# Sheet1.net
KiCad netlist of a schematic drawn in Altium Designer
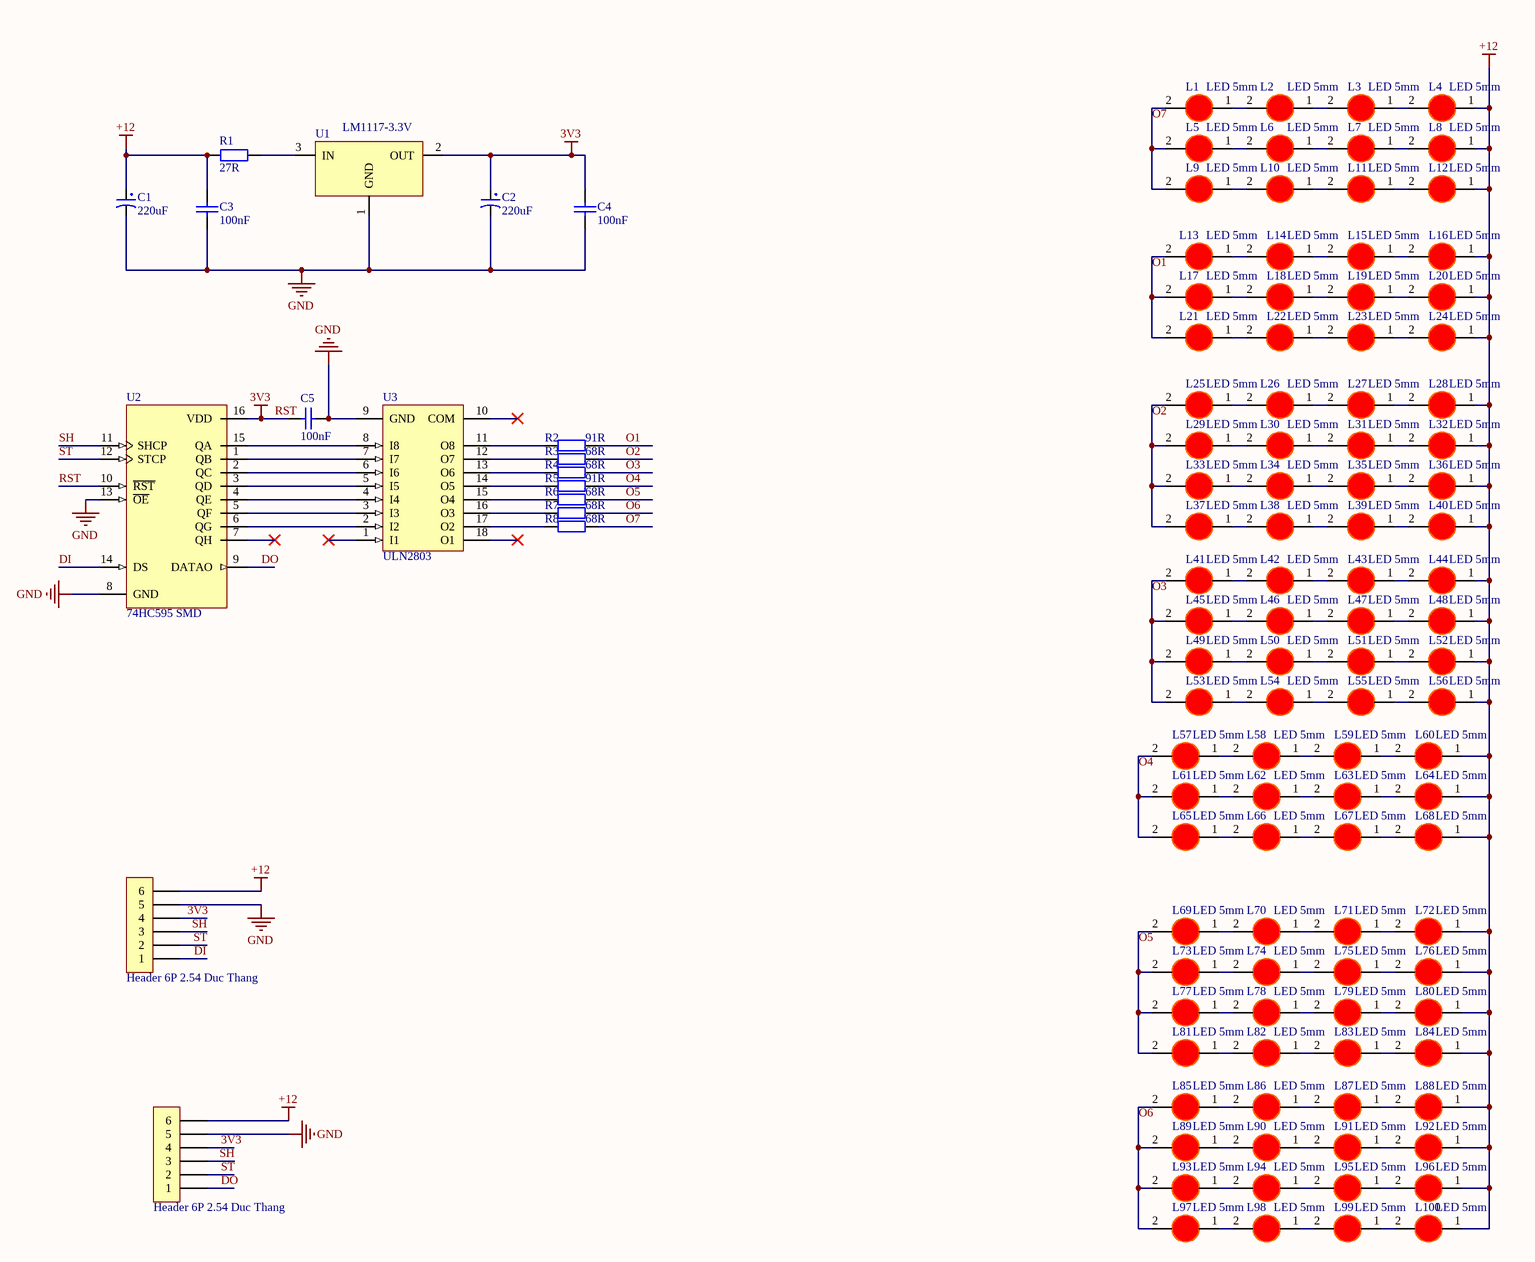
[diagram p0: Sheet1.SchDoc]

(export (version "E")
  (design (tool "Eeschema 10.0.6"))
  (components
    (comp (ref "C1")
      (value "220uF")
      (footprint "Tu hoa 5mm")
      (description "Cắm")
      (libsource (lib "Altium_Lib_by_KhueNguyenCreator") (part "Tu Hoa 220uF 16V 6x11"))
    )
    (comp (ref "C2")
      (value "220uF")
      (footprint "Tu hoa 5mm")
      (description "Cắm")
      (libsource (lib "Altium_Lib_by_KhueNguyenCreator") (part "Tu Hoa 220uF 16V 6x11"))
    )
    (comp (ref "C3")
      (value "100nF")
      (footprint "tu 0805")
      (description "Dán")
      (libsource (lib "Altium_Lib_by_KhueNguyenCreator") (part "Tu 0805 101 50V 20%"))
    )
    (comp (ref "C4")
      (value "100nF")
      (footprint "tu 0805")
      (description "Dán")
      (libsource (lib "Altium_Lib_by_KhueNguyenCreator") (part "Tu 0805 101 50V 20%"))
    )
    (comp (ref "C5")
      (value "100nF")
      (footprint "tu 0805")
      (description "Dán")
      (libsource (lib "Altium_Lib_by_KhueNguyenCreator") (part "Tu 0805 101 50V 20%"))
    )
    (comp (ref "H1")
      (value "Header 6P 2.54 Duc Thang")
      (footprint "XH2.54M-6")
      (description "Cắm")
      (libsource (lib "Altium_Lib_by_KhueNguyenCreator") (part "Header 6P 2.54 Duc Thang"))
    )
    (comp (ref "H2")
      (value "Header 6P 2.54 Duc Thang")
      (footprint "XH2.54M-6")
      (description "Cắm")
      (libsource (lib "Altium_Lib_by_KhueNguyenCreator") (part "Header 6P 2.54 Duc Thang"))
    )
    (comp (ref "L1")
      (value "LED 5mm")
      (footprint "LED-5MM-RED")
      (description "Cắm")
      (libsource (lib "Altium_Lib_by_KhueNguyenCreator") (part "LED 5mm Do"))
    )
    (comp (ref "L2")
      (value "LED 5mm")
      (footprint "LED-5MM-RED")
      (description "Cắm")
      (libsource (lib "Altium_Lib_by_KhueNguyenCreator") (part "LED 5mm Do"))
    )
    (comp (ref "L3")
      (value "LED 5mm")
      (footprint "LED-5MM-RED")
      (description "Cắm")
      (libsource (lib "Altium_Lib_by_KhueNguyenCreator") (part "LED 5mm Do"))
    )
    (comp (ref "L4")
      (value "LED 5mm")
      (footprint "LED-5MM-RED")
      (description "Cắm")
      (libsource (lib "Altium_Lib_by_KhueNguyenCreator") (part "LED 5mm Do"))
    )
    (comp (ref "L5")
      (value "LED 5mm")
      (footprint "LED-5MM-RED")
      (description "Cắm")
      (libsource (lib "Altium_Lib_by_KhueNguyenCreator") (part "LED 5mm Do"))
    )
    (comp (ref "L6")
      (value "LED 5mm")
      (footprint "LED-5MM-RED")
      (description "Cắm")
      (libsource (lib "Altium_Lib_by_KhueNguyenCreator") (part "LED 5mm Do"))
    )
    (comp (ref "L7")
      (value "LED 5mm")
      (footprint "LED-5MM-RED")
      (description "Cắm")
      (libsource (lib "Altium_Lib_by_KhueNguyenCreator") (part "LED 5mm Do"))
    )
    (comp (ref "L8")
      (value "LED 5mm")
      (footprint "LED-5MM-RED")
      (description "Cắm")
      (libsource (lib "Altium_Lib_by_KhueNguyenCreator") (part "LED 5mm Do"))
    )
    (comp (ref "L9")
      (value "LED 5mm")
      (footprint "LED-5MM-RED")
      (description "Cắm")
      (libsource (lib "Altium_Lib_by_KhueNguyenCreator") (part "LED 5mm Do"))
    )
    (comp (ref "L10")
      (value "LED 5mm")
      (footprint "LED-5MM-RED")
      (description "Cắm")
      (libsource (lib "Altium_Lib_by_KhueNguyenCreator") (part "LED 5mm Do"))
    )
    (comp (ref "L11")
      (value "LED 5mm")
      (footprint "LED-5MM-RED")
      (description "Cắm")
      (libsource (lib "Altium_Lib_by_KhueNguyenCreator") (part "LED 5mm Do"))
    )
    (comp (ref "L12")
      (value "LED 5mm")
      (footprint "LED-5MM-RED")
      (description "Cắm")
      (libsource (lib "Altium_Lib_by_KhueNguyenCreator") (part "LED 5mm Do"))
    )
    (comp (ref "L13")
      (value "LED 5mm")
      (footprint "LED-5MM-RED")
      (description "Cắm")
      (libsource (lib "Altium_Lib_by_KhueNguyenCreator") (part "LED 5mm Do"))
    )
    (comp (ref "L14")
      (value "LED 5mm")
      (footprint "LED-5MM-RED")
      (description "Cắm")
      (libsource (lib "Altium_Lib_by_KhueNguyenCreator") (part "LED 5mm Do"))
    )
    (comp (ref "L15")
      (value "LED 5mm")
      (footprint "LED-5MM-RED")
      (description "Cắm")
      (libsource (lib "Altium_Lib_by_KhueNguyenCreator") (part "LED 5mm Do"))
    )
    (comp (ref "L16")
      (value "LED 5mm")
      (footprint "LED-5MM-RED")
      (description "Cắm")
      (libsource (lib "Altium_Lib_by_KhueNguyenCreator") (part "LED 5mm Do"))
    )
    (comp (ref "L17")
      (value "LED 5mm")
      (footprint "LED-5MM-RED")
      (description "Cắm")
      (libsource (lib "Altium_Lib_by_KhueNguyenCreator") (part "LED 5mm Do"))
    )
    (comp (ref "L18")
      (value "LED 5mm")
      (footprint "LED-5MM-RED")
      (description "Cắm")
      (libsource (lib "Altium_Lib_by_KhueNguyenCreator") (part "LED 5mm Do"))
    )
    (comp (ref "L19")
      (value "LED 5mm")
      (footprint "LED-5MM-RED")
      (description "Cắm")
      (libsource (lib "Altium_Lib_by_KhueNguyenCreator") (part "LED 5mm Do"))
    )
    (comp (ref "L20")
      (value "LED 5mm")
      (footprint "LED-5MM-RED")
      (description "Cắm")
      (libsource (lib "Altium_Lib_by_KhueNguyenCreator") (part "LED 5mm Do"))
    )
    (comp (ref "L21")
      (value "LED 5mm")
      (footprint "LED-5MM-RED")
      (description "Cắm")
      (libsource (lib "Altium_Lib_by_KhueNguyenCreator") (part "LED 5mm Do"))
    )
    (comp (ref "L22")
      (value "LED 5mm")
      (footprint "LED-5MM-RED")
      (description "Cắm")
      (libsource (lib "Altium_Lib_by_KhueNguyenCreator") (part "LED 5mm Do"))
    )
    (comp (ref "L23")
      (value "LED 5mm")
      (footprint "LED-5MM-RED")
      (description "Cắm")
      (libsource (lib "Altium_Lib_by_KhueNguyenCreator") (part "LED 5mm Do"))
    )
    (comp (ref "L24")
      (value "LED 5mm")
      (footprint "LED-5MM-RED")
      (description "Cắm")
      (libsource (lib "Altium_Lib_by_KhueNguyenCreator") (part "LED 5mm Do"))
    )
    (comp (ref "L25")
      (value "LED 5mm")
      (footprint "LED-5MM-RED")
      (description "Cắm")
      (libsource (lib "Altium_Lib_by_KhueNguyenCreator") (part "LED 5mm Do"))
    )
    (comp (ref "L26")
      (value "LED 5mm")
      (footprint "LED-5MM-RED")
      (description "Cắm")
      (libsource (lib "Altium_Lib_by_KhueNguyenCreator") (part "LED 5mm Do"))
    )
    (comp (ref "L27")
      (value "LED 5mm")
      (footprint "LED-5MM-RED")
      (description "Cắm")
      (libsource (lib "Altium_Lib_by_KhueNguyenCreator") (part "LED 5mm Do"))
    )
    (comp (ref "L28")
      (value "LED 5mm")
      (footprint "LED-5MM-RED")
      (description "Cắm")
      (libsource (lib "Altium_Lib_by_KhueNguyenCreator") (part "LED 5mm Do"))
    )
    (comp (ref "L29")
      (value "LED 5mm")
      (footprint "LED-5MM-RED")
      (description "Cắm")
      (libsource (lib "Altium_Lib_by_KhueNguyenCreator") (part "LED 5mm Do"))
    )
    (comp (ref "L30")
      (value "LED 5mm")
      (footprint "LED-5MM-RED")
      (description "Cắm")
      (libsource (lib "Altium_Lib_by_KhueNguyenCreator") (part "LED 5mm Do"))
    )
    (comp (ref "L31")
      (value "LED 5mm")
      (footprint "LED-5MM-RED")
      (description "Cắm")
      (libsource (lib "Altium_Lib_by_KhueNguyenCreator") (part "LED 5mm Do"))
    )
    (comp (ref "L32")
      (value "LED 5mm")
      (footprint "LED-5MM-RED")
      (description "Cắm")
      (libsource (lib "Altium_Lib_by_KhueNguyenCreator") (part "LED 5mm Do"))
    )
    (comp (ref "L33")
      (value "LED 5mm")
      (footprint "LED-5MM-RED")
      (description "Cắm")
      (libsource (lib "Altium_Lib_by_KhueNguyenCreator") (part "LED 5mm Do"))
    )
    (comp (ref "L34")
      (value "LED 5mm")
      (footprint "LED-5MM-RED")
      (description "Cắm")
      (libsource (lib "Altium_Lib_by_KhueNguyenCreator") (part "LED 5mm Do"))
    )
    (comp (ref "L35")
      (value "LED 5mm")
      (footprint "LED-5MM-RED")
      (description "Cắm")
      (libsource (lib "Altium_Lib_by_KhueNguyenCreator") (part "LED 5mm Do"))
    )
    (comp (ref "L36")
      (value "LED 5mm")
      (footprint "LED-5MM-RED")
      (description "Cắm")
      (libsource (lib "Altium_Lib_by_KhueNguyenCreator") (part "LED 5mm Do"))
    )
    (comp (ref "L37")
      (value "LED 5mm")
      (footprint "LED-5MM-RED")
      (description "Cắm")
      (libsource (lib "Altium_Lib_by_KhueNguyenCreator") (part "LED 5mm Do"))
    )
    (comp (ref "L38")
      (value "LED 5mm")
      (footprint "LED-5MM-RED")
      (description "Cắm")
      (libsource (lib "Altium_Lib_by_KhueNguyenCreator") (part "LED 5mm Do"))
    )
    (comp (ref "L39")
      (value "LED 5mm")
      (footprint "LED-5MM-RED")
      (description "Cắm")
      (libsource (lib "Altium_Lib_by_KhueNguyenCreator") (part "LED 5mm Do"))
    )
    (comp (ref "L40")
      (value "LED 5mm")
      (footprint "LED-5MM-RED")
      (description "Cắm")
      (libsource (lib "Altium_Lib_by_KhueNguyenCreator") (part "LED 5mm Do"))
    )
    (comp (ref "L41")
      (value "LED 5mm")
      (footprint "LED-5MM-RED")
      (description "Cắm")
      (libsource (lib "Altium_Lib_by_KhueNguyenCreator") (part "LED 5mm Do"))
    )
    (comp (ref "L42")
      (value "LED 5mm")
      (footprint "LED-5MM-RED")
      (description "Cắm")
      (libsource (lib "Altium_Lib_by_KhueNguyenCreator") (part "LED 5mm Do"))
    )
    (comp (ref "L43")
      (value "LED 5mm")
      (footprint "LED-5MM-RED")
      (description "Cắm")
      (libsource (lib "Altium_Lib_by_KhueNguyenCreator") (part "LED 5mm Do"))
    )
    (comp (ref "L44")
      (value "LED 5mm")
      (footprint "LED-5MM-RED")
      (description "Cắm")
      (libsource (lib "Altium_Lib_by_KhueNguyenCreator") (part "LED 5mm Do"))
    )
    (comp (ref "L45")
      (value "LED 5mm")
      (footprint "LED-5MM-RED")
      (description "Cắm")
      (libsource (lib "Altium_Lib_by_KhueNguyenCreator") (part "LED 5mm Do"))
    )
    (comp (ref "L46")
      (value "LED 5mm")
      (footprint "LED-5MM-RED")
      (description "Cắm")
      (libsource (lib "Altium_Lib_by_KhueNguyenCreator") (part "LED 5mm Do"))
    )
    (comp (ref "L47")
      (value "LED 5mm")
      (footprint "LED-5MM-RED")
      (description "Cắm")
      (libsource (lib "Altium_Lib_by_KhueNguyenCreator") (part "LED 5mm Do"))
    )
    (comp (ref "L48")
      (value "LED 5mm")
      (footprint "LED-5MM-RED")
      (description "Cắm")
      (libsource (lib "Altium_Lib_by_KhueNguyenCreator") (part "LED 5mm Do"))
    )
    (comp (ref "L49")
      (value "LED 5mm")
      (footprint "LED-5MM-RED")
      (description "Cắm")
      (libsource (lib "Altium_Lib_by_KhueNguyenCreator") (part "LED 5mm Do"))
    )
    (comp (ref "L50")
      (value "LED 5mm")
      (footprint "LED-5MM-RED")
      (description "Cắm")
      (libsource (lib "Altium_Lib_by_KhueNguyenCreator") (part "LED 5mm Do"))
    )
    (comp (ref "L51")
      (value "LED 5mm")
      (footprint "LED-5MM-RED")
      (description "Cắm")
      (libsource (lib "Altium_Lib_by_KhueNguyenCreator") (part "LED 5mm Do"))
    )
    (comp (ref "L52")
      (value "LED 5mm")
      (footprint "LED-5MM-RED")
      (description "Cắm")
      (libsource (lib "Altium_Lib_by_KhueNguyenCreator") (part "LED 5mm Do"))
    )
    (comp (ref "L53")
      (value "LED 5mm")
      (footprint "LED-5MM-RED")
      (description "Cắm")
      (libsource (lib "Altium_Lib_by_KhueNguyenCreator") (part "LED 5mm Do"))
    )
    (comp (ref "L54")
      (value "LED 5mm")
      (footprint "LED-5MM-RED")
      (description "Cắm")
      (libsource (lib "Altium_Lib_by_KhueNguyenCreator") (part "LED 5mm Do"))
    )
    (comp (ref "L55")
      (value "LED 5mm")
      (footprint "LED-5MM-RED")
      (description "Cắm")
      (libsource (lib "Altium_Lib_by_KhueNguyenCreator") (part "LED 5mm Do"))
    )
    (comp (ref "L56")
      (value "LED 5mm")
      (footprint "LED-5MM-RED")
      (description "Cắm")
      (libsource (lib "Altium_Lib_by_KhueNguyenCreator") (part "LED 5mm Do"))
    )
    (comp (ref "L57")
      (value "LED 5mm")
      (footprint "LED-5MM-RED")
      (description "Cắm")
      (libsource (lib "Altium_Lib_by_KhueNguyenCreator") (part "LED 5mm Do"))
    )
    (comp (ref "L58")
      (value "LED 5mm")
      (footprint "LED-5MM-RED")
      (description "Cắm")
      (libsource (lib "Altium_Lib_by_KhueNguyenCreator") (part "LED 5mm Do"))
    )
    (comp (ref "L59")
      (value "LED 5mm")
      (footprint "LED-5MM-RED")
      (description "Cắm")
      (libsource (lib "Altium_Lib_by_KhueNguyenCreator") (part "LED 5mm Do"))
    )
    (comp (ref "L60")
      (value "LED 5mm")
      (footprint "LED-5MM-RED")
      (description "Cắm")
      (libsource (lib "Altium_Lib_by_KhueNguyenCreator") (part "LED 5mm Do"))
    )
    (comp (ref "L61")
      (value "LED 5mm")
      (footprint "LED-5MM-RED")
      (description "Cắm")
      (libsource (lib "Altium_Lib_by_KhueNguyenCreator") (part "LED 5mm Do"))
    )
    (comp (ref "L62")
      (value "LED 5mm")
      (footprint "LED-5MM-RED")
      (description "Cắm")
      (libsource (lib "Altium_Lib_by_KhueNguyenCreator") (part "LED 5mm Do"))
    )
    (comp (ref "L63")
      (value "LED 5mm")
      (footprint "LED-5MM-RED")
      (description "Cắm")
      (libsource (lib "Altium_Lib_by_KhueNguyenCreator") (part "LED 5mm Do"))
    )
    (comp (ref "L64")
      (value "LED 5mm")
      (footprint "LED-5MM-RED")
      (description "Cắm")
      (libsource (lib "Altium_Lib_by_KhueNguyenCreator") (part "LED 5mm Do"))
    )
    (comp (ref "L65")
      (value "LED 5mm")
      (footprint "LED-5MM-RED")
      (description "Cắm")
      (libsource (lib "Altium_Lib_by_KhueNguyenCreator") (part "LED 5mm Do"))
    )
    (comp (ref "L66")
      (value "LED 5mm")
      (footprint "LED-5MM-RED")
      (description "Cắm")
      (libsource (lib "Altium_Lib_by_KhueNguyenCreator") (part "LED 5mm Do"))
    )
    (comp (ref "L67")
      (value "LED 5mm")
      (footprint "LED-5MM-RED")
      (description "Cắm")
      (libsource (lib "Altium_Lib_by_KhueNguyenCreator") (part "LED 5mm Do"))
    )
    (comp (ref "L68")
      (value "LED 5mm")
      (footprint "LED-5MM-RED")
      (description "Cắm")
      (libsource (lib "Altium_Lib_by_KhueNguyenCreator") (part "LED 5mm Do"))
    )
    (comp (ref "L69")
      (value "LED 5mm")
      (footprint "LED-5MM-RED")
      (description "Cắm")
      (libsource (lib "Altium_Lib_by_KhueNguyenCreator") (part "LED 5mm Do"))
    )
    (comp (ref "L70")
      (value "LED 5mm")
      (footprint "LED-5MM-RED")
      (description "Cắm")
      (libsource (lib "Altium_Lib_by_KhueNguyenCreator") (part "LED 5mm Do"))
    )
    (comp (ref "L71")
      (value "LED 5mm")
      (footprint "LED-5MM-RED")
      (description "Cắm")
      (libsource (lib "Altium_Lib_by_KhueNguyenCreator") (part "LED 5mm Do"))
    )
    (comp (ref "L72")
      (value "LED 5mm")
      (footprint "LED-5MM-RED")
      (description "Cắm")
      (libsource (lib "Altium_Lib_by_KhueNguyenCreator") (part "LED 5mm Do"))
    )
    (comp (ref "L73")
      (value "LED 5mm")
      (footprint "LED-5MM-RED")
      (description "Cắm")
      (libsource (lib "Altium_Lib_by_KhueNguyenCreator") (part "LED 5mm Do"))
    )
    (comp (ref "L74")
      (value "LED 5mm")
      (footprint "LED-5MM-RED")
      (description "Cắm")
      (libsource (lib "Altium_Lib_by_KhueNguyenCreator") (part "LED 5mm Do"))
    )
    (comp (ref "L75")
      (value "LED 5mm")
      (footprint "LED-5MM-RED")
      (description "Cắm")
      (libsource (lib "Altium_Lib_by_KhueNguyenCreator") (part "LED 5mm Do"))
    )
    (comp (ref "L76")
      (value "LED 5mm")
      (footprint "LED-5MM-RED")
      (description "Cắm")
      (libsource (lib "Altium_Lib_by_KhueNguyenCreator") (part "LED 5mm Do"))
    )
    (comp (ref "L77")
      (value "LED 5mm")
      (footprint "LED-5MM-RED")
      (description "Cắm")
      (libsource (lib "Altium_Lib_by_KhueNguyenCreator") (part "LED 5mm Do"))
    )
    (comp (ref "L78")
      (value "LED 5mm")
      (footprint "LED-5MM-RED")
      (description "Cắm")
      (libsource (lib "Altium_Lib_by_KhueNguyenCreator") (part "LED 5mm Do"))
    )
    (comp (ref "L79")
      (value "LED 5mm")
      (footprint "LED-5MM-RED")
      (description "Cắm")
      (libsource (lib "Altium_Lib_by_KhueNguyenCreator") (part "LED 5mm Do"))
    )
    (comp (ref "L80")
      (value "LED 5mm")
      (footprint "LED-5MM-RED")
      (description "Cắm")
      (libsource (lib "Altium_Lib_by_KhueNguyenCreator") (part "LED 5mm Do"))
    )
    (comp (ref "L81")
      (value "LED 5mm")
      (footprint "LED-5MM-RED")
      (description "Cắm")
      (libsource (lib "Altium_Lib_by_KhueNguyenCreator") (part "LED 5mm Do"))
    )
    (comp (ref "L82")
      (value "LED 5mm")
      (footprint "LED-5MM-RED")
      (description "Cắm")
      (libsource (lib "Altium_Lib_by_KhueNguyenCreator") (part "LED 5mm Do"))
    )
    (comp (ref "L83")
      (value "LED 5mm")
      (footprint "LED-5MM-RED")
      (description "Cắm")
      (libsource (lib "Altium_Lib_by_KhueNguyenCreator") (part "LED 5mm Do"))
    )
    (comp (ref "L84")
      (value "LED 5mm")
      (footprint "LED-5MM-RED")
      (description "Cắm")
      (libsource (lib "Altium_Lib_by_KhueNguyenCreator") (part "LED 5mm Do"))
    )
    (comp (ref "L85")
      (value "LED 5mm")
      (footprint "LED-5MM-RED")
      (description "Cắm")
      (libsource (lib "Altium_Lib_by_KhueNguyenCreator") (part "LED 5mm Do"))
    )
    (comp (ref "L86")
      (value "LED 5mm")
      (footprint "LED-5MM-RED")
      (description "Cắm")
      (libsource (lib "Altium_Lib_by_KhueNguyenCreator") (part "LED 5mm Do"))
    )
    (comp (ref "L87")
      (value "LED 5mm")
      (footprint "LED-5MM-RED")
      (description "Cắm")
      (libsource (lib "Altium_Lib_by_KhueNguyenCreator") (part "LED 5mm Do"))
    )
    (comp (ref "L88")
      (value "LED 5mm")
      (footprint "LED-5MM-RED")
      (description "Cắm")
      (libsource (lib "Altium_Lib_by_KhueNguyenCreator") (part "LED 5mm Do"))
    )
    (comp (ref "L89")
      (value "LED 5mm")
      (footprint "LED-5MM-RED")
      (description "Cắm")
      (libsource (lib "Altium_Lib_by_KhueNguyenCreator") (part "LED 5mm Do"))
    )
    (comp (ref "L90")
      (value "LED 5mm")
      (footprint "LED-5MM-RED")
      (description "Cắm")
      (libsource (lib "Altium_Lib_by_KhueNguyenCreator") (part "LED 5mm Do"))
    )
    (comp (ref "L91")
      (value "LED 5mm")
      (footprint "LED-5MM-RED")
      (description "Cắm")
      (libsource (lib "Altium_Lib_by_KhueNguyenCreator") (part "LED 5mm Do"))
    )
    (comp (ref "L92")
      (value "LED 5mm")
      (footprint "LED-5MM-RED")
      (description "Cắm")
      (libsource (lib "Altium_Lib_by_KhueNguyenCreator") (part "LED 5mm Do"))
    )
    (comp (ref "L93")
      (value "LED 5mm")
      (footprint "LED-5MM-RED")
      (description "Cắm")
      (libsource (lib "Altium_Lib_by_KhueNguyenCreator") (part "LED 5mm Do"))
    )
    (comp (ref "L94")
      (value "LED 5mm")
      (footprint "LED-5MM-RED")
      (description "Cắm")
      (libsource (lib "Altium_Lib_by_KhueNguyenCreator") (part "LED 5mm Do"))
    )
    (comp (ref "L95")
      (value "LED 5mm")
      (footprint "LED-5MM-RED")
      (description "Cắm")
      (libsource (lib "Altium_Lib_by_KhueNguyenCreator") (part "LED 5mm Do"))
    )
    (comp (ref "L96")
      (value "LED 5mm")
      (footprint "LED-5MM-RED")
      (description "Cắm")
      (libsource (lib "Altium_Lib_by_KhueNguyenCreator") (part "LED 5mm Do"))
    )
    (comp (ref "L97")
      (value "LED 5mm")
      (footprint "LED-5MM-RED")
      (description "Cắm")
      (libsource (lib "Altium_Lib_by_KhueNguyenCreator") (part "LED 5mm Do"))
    )
    (comp (ref "L98")
      (value "LED 5mm")
      (footprint "LED-5MM-RED")
      (description "Cắm")
      (libsource (lib "Altium_Lib_by_KhueNguyenCreator") (part "LED 5mm Do"))
    )
    (comp (ref "L99")
      (value "LED 5mm")
      (footprint "LED-5MM-RED")
      (description "Cắm")
      (libsource (lib "Altium_Lib_by_KhueNguyenCreator") (part "LED 5mm Do"))
    )
    (comp (ref "L100")
      (value "LED 5mm")
      (footprint "LED-5MM-RED")
      (description "Cắm")
      (libsource (lib "Altium_Lib_by_KhueNguyenCreator") (part "LED 5mm Do"))
    )
    (comp (ref "R1")
      (value "27R")
      (footprint "tro smd 1206")
      (description "Dán")
      (libsource (lib "Altium_Lib_by_KhueNguyenCreator") (part "Tro 1206 1% 10R"))
    )
    (comp (ref "R2")
      (value "91R")
      (footprint "tro smd 1206")
      (description "Dán")
      (libsource (lib "Altium_Lib_by_KhueNguyenCreator") (part "Tro 1206 5% 1.5k"))
    )
    (comp (ref "R3")
      (value "68R")
      (footprint "tro smd 1206")
      (description "Dán")
      (libsource (lib "Altium_Lib_by_KhueNguyenCreator") (part "Tro 1206 5% 1.5k"))
    )
    (comp (ref "R4")
      (value "68R")
      (footprint "tro smd 1206")
      (description "Dán")
      (libsource (lib "Altium_Lib_by_KhueNguyenCreator") (part "Tro 1206 5% 1.5k"))
    )
    (comp (ref "R5")
      (value "91R")
      (footprint "tro smd 1206")
      (description "Dán")
      (libsource (lib "Altium_Lib_by_KhueNguyenCreator") (part "Tro 1206 5% 1.5k"))
    )
    (comp (ref "R6")
      (value "68R")
      (footprint "tro smd 1206")
      (description "Dán")
      (libsource (lib "Altium_Lib_by_KhueNguyenCreator") (part "Tro 1206 5% 1.5k"))
    )
    (comp (ref "R7")
      (value "68R")
      (footprint "tro smd 1206")
      (description "Dán")
      (libsource (lib "Altium_Lib_by_KhueNguyenCreator") (part "Tro 1206 5% 1.5k"))
    )
    (comp (ref "R8")
      (value "68R")
      (footprint "tro smd 1206")
      (description "Dán")
      (libsource (lib "Altium_Lib_by_KhueNguyenCreator") (part "Tro 1206 5% 1.5k"))
    )
    (comp (ref "U1")
      (value "LM1117-3.3V")
      (footprint "SOT223")
      (description "800mA Low-Dropout Linear Regulator")
      (fields (field (name "CREATOR") "Nguyen Ba Bien"))
      (libsource (lib "TechMT.VN_Lib_Project v2") (part "LM1117"))
    )
    (comp (ref "U2")
      (value "74HC595 SMD")
      (footprint "SOP 16")
      (description "Dán")
      (libsource (lib "Altium_Lib_by_KhueNguyenCreator") (part "74HC595 SMD"))
    )
    (comp (ref "U3")
      (value "ULN2803")
      (footprint "SOP 18")
      (description "Dán")
      (libsource (lib "Altium_Lib_by_KhueNguyenCreator") (part "ULN2803A SMD"))
    )
  )
  (nets
    (net (code "1") (name "+12") (class "Default")
      (node (ref "C1") (pin "1") (pinfunction "1_1") (pintype "passive"))
      (node (ref "C3") (pin "1") (pinfunction "1_1") (pintype "passive"))
      (node (ref "H1") (pin "6") (pinfunction "6_6") (pintype "passive"))
      (node (ref "H2") (pin "6") (pinfunction "6_6") (pintype "passive"))
      (node (ref "L100") (pin "1") (pinfunction "A_1") (pintype "passive"))
      (node (ref "L12") (pin "1") (pinfunction "A_1") (pintype "passive"))
      (node (ref "L16") (pin "1") (pinfunction "A_1") (pintype "passive"))
      (node (ref "L20") (pin "1") (pinfunction "A_1") (pintype "passive"))
      (node (ref "L24") (pin "1") (pinfunction "A_1") (pintype "passive"))
      (node (ref "L28") (pin "1") (pinfunction "A_1") (pintype "passive"))
      (node (ref "L32") (pin "1") (pinfunction "A_1") (pintype "passive"))
      (node (ref "L36") (pin "1") (pinfunction "A_1") (pintype "passive"))
      (node (ref "L4") (pin "1") (pinfunction "A_1") (pintype "passive"))
      (node (ref "L40") (pin "1") (pinfunction "A_1") (pintype "passive"))
      (node (ref "L44") (pin "1") (pinfunction "A_1") (pintype "passive"))
      (node (ref "L48") (pin "1") (pinfunction "A_1") (pintype "passive"))
      (node (ref "L52") (pin "1") (pinfunction "A_1") (pintype "passive"))
      (node (ref "L56") (pin "1") (pinfunction "A_1") (pintype "passive"))
      (node (ref "L60") (pin "1") (pinfunction "A_1") (pintype "passive"))
      (node (ref "L64") (pin "1") (pinfunction "A_1") (pintype "passive"))
      (node (ref "L68") (pin "1") (pinfunction "A_1") (pintype "passive"))
      (node (ref "L72") (pin "1") (pinfunction "A_1") (pintype "passive"))
      (node (ref "L76") (pin "1") (pinfunction "A_1") (pintype "passive"))
      (node (ref "L8") (pin "1") (pinfunction "A_1") (pintype "passive"))
      (node (ref "L80") (pin "1") (pinfunction "A_1") (pintype "passive"))
      (node (ref "L84") (pin "1") (pinfunction "A_1") (pintype "passive"))
      (node (ref "L88") (pin "1") (pinfunction "A_1") (pintype "passive"))
      (node (ref "L92") (pin "1") (pinfunction "A_1") (pintype "passive"))
      (node (ref "L96") (pin "1") (pinfunction "A_1") (pintype "passive"))
      (node (ref "R1") (pin "1") (pinfunction "1_1") (pintype "passive"))
    )
    (net (code "2") (name "/DI") (class "Default")
      (node (ref "H1") (pin "1") (pinfunction "1_1") (pintype "passive"))
      (node (ref "U2") (pin "14") (pinfunction "DS_14") (pintype "input"))
    )
    (net (code "3") (name "/DO") (class "Default")
      (node (ref "H2") (pin "1") (pinfunction "1_1") (pintype "passive"))
      (node (ref "U2") (pin "9") (pinfunction "DATAO_9") (pintype "output"))
    )
    (net (code "4") (name "/O1") (class "Default")
      (node (ref "L13") (pin "2") (pinfunction "K_2") (pintype "passive"))
      (node (ref "L17") (pin "2") (pinfunction "K_2") (pintype "passive"))
      (node (ref "L21") (pin "2") (pinfunction "K_2") (pintype "passive"))
      (node (ref "R2") (pin "2") (pinfunction "2_2") (pintype "passive"))
    )
    (net (code "5") (name "/O2") (class "Default")
      (node (ref "L25") (pin "2") (pinfunction "K_2") (pintype "passive"))
      (node (ref "L29") (pin "2") (pinfunction "K_2") (pintype "passive"))
      (node (ref "L33") (pin "2") (pinfunction "K_2") (pintype "passive"))
      (node (ref "L37") (pin "2") (pinfunction "K_2") (pintype "passive"))
      (node (ref "R3") (pin "2") (pinfunction "2_2") (pintype "passive"))
    )
    (net (code "6") (name "/O3") (class "Default")
      (node (ref "L41") (pin "2") (pinfunction "K_2") (pintype "passive"))
      (node (ref "L45") (pin "2") (pinfunction "K_2") (pintype "passive"))
      (node (ref "L49") (pin "2") (pinfunction "K_2") (pintype "passive"))
      (node (ref "L53") (pin "2") (pinfunction "K_2") (pintype "passive"))
      (node (ref "R4") (pin "2") (pinfunction "2_2") (pintype "passive"))
    )
    (net (code "7") (name "/O4") (class "Default")
      (node (ref "L57") (pin "2") (pinfunction "K_2") (pintype "passive"))
      (node (ref "L61") (pin "2") (pinfunction "K_2") (pintype "passive"))
      (node (ref "L65") (pin "2") (pinfunction "K_2") (pintype "passive"))
      (node (ref "R5") (pin "2") (pinfunction "2_2") (pintype "passive"))
    )
    (net (code "8") (name "/O5") (class "Default")
      (node (ref "L69") (pin "2") (pinfunction "K_2") (pintype "passive"))
      (node (ref "L73") (pin "2") (pinfunction "K_2") (pintype "passive"))
      (node (ref "L77") (pin "2") (pinfunction "K_2") (pintype "passive"))
      (node (ref "L81") (pin "2") (pinfunction "K_2") (pintype "passive"))
      (node (ref "R6") (pin "2") (pinfunction "2_2") (pintype "passive"))
    )
    (net (code "9") (name "/O6") (class "Default")
      (node (ref "L85") (pin "2") (pinfunction "K_2") (pintype "passive"))
      (node (ref "L89") (pin "2") (pinfunction "K_2") (pintype "passive"))
      (node (ref "L93") (pin "2") (pinfunction "K_2") (pintype "passive"))
      (node (ref "L97") (pin "2") (pinfunction "K_2") (pintype "passive"))
      (node (ref "R7") (pin "2") (pinfunction "2_2") (pintype "passive"))
    )
    (net (code "10") (name "/O7") (class "Default")
      (node (ref "L1") (pin "2") (pinfunction "K_2") (pintype "passive"))
      (node (ref "L5") (pin "2") (pinfunction "K_2") (pintype "passive"))
      (node (ref "L9") (pin "2") (pinfunction "K_2") (pintype "passive"))
      (node (ref "R8") (pin "2") (pinfunction "2_2") (pintype "passive"))
    )
    (net (code "11") (name "/SH") (class "Default")
      (node (ref "H1") (pin "3") (pinfunction "3_3") (pintype "passive"))
      (node (ref "H2") (pin "3") (pinfunction "3_3") (pintype "passive"))
      (node (ref "U2") (pin "11") (pinfunction "SHCP_11") (pintype "input"))
    )
    (net (code "12") (name "/ST") (class "Default")
      (node (ref "H1") (pin "2") (pinfunction "2_2") (pintype "passive"))
      (node (ref "H2") (pin "2") (pinfunction "2_2") (pintype "passive"))
      (node (ref "U2") (pin "12") (pinfunction "STCP_12") (pintype "input"))
    )
    (net (code "13") (name "3V3") (class "Default")
      (node (ref "C2") (pin "1") (pinfunction "1_1") (pintype "passive"))
      (node (ref "C4") (pin "1") (pinfunction "1_1") (pintype "passive"))
      (node (ref "C5") (pin "1") (pinfunction "1_1") (pintype "passive"))
      (node (ref "H1") (pin "4") (pinfunction "4_4") (pintype "passive"))
      (node (ref "H2") (pin "4") (pinfunction "4_4") (pintype "passive"))
      (node (ref "U1") (pin "2") (pinfunction "OUT_2") (pintype "passive"))
      (node (ref "U2") (pin "10") (pinfunction "~{RST}_10") (pintype "input"))
      (node (ref "U2") (pin "16") (pinfunction "VDD_16") (pintype "power_in"))
    )
    (net (code "14") (name "GND") (class "Default")
      (node (ref "C1") (pin "2") (pinfunction "2_2") (pintype "passive"))
      (node (ref "C2") (pin "2") (pinfunction "2_2") (pintype "passive"))
      (node (ref "C3") (pin "2") (pinfunction "2_2") (pintype "passive"))
      (node (ref "C4") (pin "2") (pinfunction "2_2") (pintype "passive"))
      (node (ref "C5") (pin "2") (pinfunction "2_2") (pintype "passive"))
      (node (ref "H1") (pin "5") (pinfunction "5_5") (pintype "passive"))
      (node (ref "H2") (pin "5") (pinfunction "5_5") (pintype "passive"))
      (node (ref "U1") (pin "1") (pinfunction "GND_1") (pintype "passive"))
      (node (ref "U2") (pin "13") (pinfunction "~{OE}_13") (pintype "input"))
      (node (ref "U2") (pin "8") (pinfunction "GND_8") (pintype "power_in"))
      (node (ref "U3") (pin "9") (pinfunction "GND_9") (pintype "power_in"))
    )
    (net (code "15") (name "Net-(L1-A)") (class "Default")
      (node (ref "L1") (pin "1") (pinfunction "A_1") (pintype "passive"))
      (node (ref "L2") (pin "2") (pinfunction "K_2") (pintype "passive"))
    )
    (net (code "16") (name "Net-(L2-A)") (class "Default")
      (node (ref "L2") (pin "1") (pinfunction "A_1") (pintype "passive"))
      (node (ref "L3") (pin "2") (pinfunction "K_2") (pintype "passive"))
    )
    (net (code "17") (name "Net-(L3-A)") (class "Default")
      (node (ref "L3") (pin "1") (pinfunction "A_1") (pintype "passive"))
      (node (ref "L4") (pin "2") (pinfunction "K_2") (pintype "passive"))
    )
    (net (code "18") (name "Net-(L5-A)") (class "Default")
      (node (ref "L5") (pin "1") (pinfunction "A_1") (pintype "passive"))
      (node (ref "L6") (pin "2") (pinfunction "K_2") (pintype "passive"))
    )
    (net (code "19") (name "Net-(L6-A)") (class "Default")
      (node (ref "L6") (pin "1") (pinfunction "A_1") (pintype "passive"))
      (node (ref "L7") (pin "2") (pinfunction "K_2") (pintype "passive"))
    )
    (net (code "20") (name "Net-(L7-A)") (class "Default")
      (node (ref "L7") (pin "1") (pinfunction "A_1") (pintype "passive"))
      (node (ref "L8") (pin "2") (pinfunction "K_2") (pintype "passive"))
    )
    (net (code "21") (name "Net-(L10-A)") (class "Default")
      (node (ref "L10") (pin "1") (pinfunction "A_1") (pintype "passive"))
      (node (ref "L11") (pin "2") (pinfunction "K_2") (pintype "passive"))
    )
    (net (code "22") (name "Net-(L10-K)") (class "Default")
      (node (ref "L10") (pin "2") (pinfunction "K_2") (pintype "passive"))
      (node (ref "L9") (pin "1") (pinfunction "A_1") (pintype "passive"))
    )
    (net (code "23") (name "Net-(L11-A)") (class "Default")
      (node (ref "L11") (pin "1") (pinfunction "A_1") (pintype "passive"))
      (node (ref "L12") (pin "2") (pinfunction "K_2") (pintype "passive"))
    )
    (net (code "24") (name "Net-(L13-A)") (class "Default")
      (node (ref "L13") (pin "1") (pinfunction "A_1") (pintype "passive"))
      (node (ref "L14") (pin "2") (pinfunction "K_2") (pintype "passive"))
    )
    (net (code "25") (name "Net-(L14-A)") (class "Default")
      (node (ref "L14") (pin "1") (pinfunction "A_1") (pintype "passive"))
      (node (ref "L15") (pin "2") (pinfunction "K_2") (pintype "passive"))
    )
    (net (code "26") (name "Net-(L15-A)") (class "Default")
      (node (ref "L15") (pin "1") (pinfunction "A_1") (pintype "passive"))
      (node (ref "L16") (pin "2") (pinfunction "K_2") (pintype "passive"))
    )
    (net (code "27") (name "Net-(L17-A)") (class "Default")
      (node (ref "L17") (pin "1") (pinfunction "A_1") (pintype "passive"))
      (node (ref "L18") (pin "2") (pinfunction "K_2") (pintype "passive"))
    )
    (net (code "28") (name "Net-(L18-A)") (class "Default")
      (node (ref "L18") (pin "1") (pinfunction "A_1") (pintype "passive"))
      (node (ref "L19") (pin "2") (pinfunction "K_2") (pintype "passive"))
    )
    (net (code "29") (name "Net-(L19-A)") (class "Default")
      (node (ref "L19") (pin "1") (pinfunction "A_1") (pintype "passive"))
      (node (ref "L20") (pin "2") (pinfunction "K_2") (pintype "passive"))
    )
    (net (code "30") (name "Net-(L21-A)") (class "Default")
      (node (ref "L21") (pin "1") (pinfunction "A_1") (pintype "passive"))
      (node (ref "L22") (pin "2") (pinfunction "K_2") (pintype "passive"))
    )
    (net (code "31") (name "Net-(L22-A)") (class "Default")
      (node (ref "L22") (pin "1") (pinfunction "A_1") (pintype "passive"))
      (node (ref "L23") (pin "2") (pinfunction "K_2") (pintype "passive"))
    )
    (net (code "32") (name "Net-(L23-A)") (class "Default")
      (node (ref "L23") (pin "1") (pinfunction "A_1") (pintype "passive"))
      (node (ref "L24") (pin "2") (pinfunction "K_2") (pintype "passive"))
    )
    (net (code "33") (name "Net-(L25-A)") (class "Default")
      (node (ref "L25") (pin "1") (pinfunction "A_1") (pintype "passive"))
      (node (ref "L26") (pin "2") (pinfunction "K_2") (pintype "passive"))
    )
    (net (code "34") (name "Net-(L26-A)") (class "Default")
      (node (ref "L26") (pin "1") (pinfunction "A_1") (pintype "passive"))
      (node (ref "L27") (pin "2") (pinfunction "K_2") (pintype "passive"))
    )
    (net (code "35") (name "Net-(L27-A)") (class "Default")
      (node (ref "L27") (pin "1") (pinfunction "A_1") (pintype "passive"))
      (node (ref "L28") (pin "2") (pinfunction "K_2") (pintype "passive"))
    )
    (net (code "36") (name "Net-(L29-A)") (class "Default")
      (node (ref "L29") (pin "1") (pinfunction "A_1") (pintype "passive"))
      (node (ref "L30") (pin "2") (pinfunction "K_2") (pintype "passive"))
    )
    (net (code "37") (name "Net-(L30-A)") (class "Default")
      (node (ref "L30") (pin "1") (pinfunction "A_1") (pintype "passive"))
      (node (ref "L31") (pin "2") (pinfunction "K_2") (pintype "passive"))
    )
    (net (code "38") (name "Net-(L31-A)") (class "Default")
      (node (ref "L31") (pin "1") (pinfunction "A_1") (pintype "passive"))
      (node (ref "L32") (pin "2") (pinfunction "K_2") (pintype "passive"))
    )
    (net (code "39") (name "Net-(L33-A)") (class "Default")
      (node (ref "L33") (pin "1") (pinfunction "A_1") (pintype "passive"))
      (node (ref "L34") (pin "2") (pinfunction "K_2") (pintype "passive"))
    )
    (net (code "40") (name "Net-(L34-A)") (class "Default")
      (node (ref "L34") (pin "1") (pinfunction "A_1") (pintype "passive"))
      (node (ref "L35") (pin "2") (pinfunction "K_2") (pintype "passive"))
    )
    (net (code "41") (name "Net-(L35-A)") (class "Default")
      (node (ref "L35") (pin "1") (pinfunction "A_1") (pintype "passive"))
      (node (ref "L36") (pin "2") (pinfunction "K_2") (pintype "passive"))
    )
    (net (code "42") (name "Net-(L37-A)") (class "Default")
      (node (ref "L37") (pin "1") (pinfunction "A_1") (pintype "passive"))
      (node (ref "L38") (pin "2") (pinfunction "K_2") (pintype "passive"))
    )
    (net (code "43") (name "Net-(L38-A)") (class "Default")
      (node (ref "L38") (pin "1") (pinfunction "A_1") (pintype "passive"))
      (node (ref "L39") (pin "2") (pinfunction "K_2") (pintype "passive"))
    )
    (net (code "44") (name "Net-(L39-A)") (class "Default")
      (node (ref "L39") (pin "1") (pinfunction "A_1") (pintype "passive"))
      (node (ref "L40") (pin "2") (pinfunction "K_2") (pintype "passive"))
    )
    (net (code "45") (name "Net-(L41-A)") (class "Default")
      (node (ref "L41") (pin "1") (pinfunction "A_1") (pintype "passive"))
      (node (ref "L42") (pin "2") (pinfunction "K_2") (pintype "passive"))
    )
    (net (code "46") (name "Net-(L42-A)") (class "Default")
      (node (ref "L42") (pin "1") (pinfunction "A_1") (pintype "passive"))
      (node (ref "L43") (pin "2") (pinfunction "K_2") (pintype "passive"))
    )
    (net (code "47") (name "Net-(L43-A)") (class "Default")
      (node (ref "L43") (pin "1") (pinfunction "A_1") (pintype "passive"))
      (node (ref "L44") (pin "2") (pinfunction "K_2") (pintype "passive"))
    )
    (net (code "48") (name "Net-(L45-A)") (class "Default")
      (node (ref "L45") (pin "1") (pinfunction "A_1") (pintype "passive"))
      (node (ref "L46") (pin "2") (pinfunction "K_2") (pintype "passive"))
    )
    (net (code "49") (name "Net-(L46-A)") (class "Default")
      (node (ref "L46") (pin "1") (pinfunction "A_1") (pintype "passive"))
      (node (ref "L47") (pin "2") (pinfunction "K_2") (pintype "passive"))
    )
    (net (code "50") (name "Net-(L47-A)") (class "Default")
      (node (ref "L47") (pin "1") (pinfunction "A_1") (pintype "passive"))
      (node (ref "L48") (pin "2") (pinfunction "K_2") (pintype "passive"))
    )
    (net (code "51") (name "Net-(L49-A)") (class "Default")
      (node (ref "L49") (pin "1") (pinfunction "A_1") (pintype "passive"))
      (node (ref "L50") (pin "2") (pinfunction "K_2") (pintype "passive"))
    )
    (net (code "52") (name "Net-(L50-A)") (class "Default")
      (node (ref "L50") (pin "1") (pinfunction "A_1") (pintype "passive"))
      (node (ref "L51") (pin "2") (pinfunction "K_2") (pintype "passive"))
    )
    (net (code "53") (name "Net-(L51-A)") (class "Default")
      (node (ref "L51") (pin "1") (pinfunction "A_1") (pintype "passive"))
      (node (ref "L52") (pin "2") (pinfunction "K_2") (pintype "passive"))
    )
    (net (code "54") (name "Net-(L53-A)") (class "Default")
      (node (ref "L53") (pin "1") (pinfunction "A_1") (pintype "passive"))
      (node (ref "L54") (pin "2") (pinfunction "K_2") (pintype "passive"))
    )
    (net (code "55") (name "Net-(L54-A)") (class "Default")
      (node (ref "L54") (pin "1") (pinfunction "A_1") (pintype "passive"))
      (node (ref "L55") (pin "2") (pinfunction "K_2") (pintype "passive"))
    )
    (net (code "56") (name "Net-(L55-A)") (class "Default")
      (node (ref "L55") (pin "1") (pinfunction "A_1") (pintype "passive"))
      (node (ref "L56") (pin "2") (pinfunction "K_2") (pintype "passive"))
    )
    (net (code "57") (name "Net-(L57-A)") (class "Default")
      (node (ref "L57") (pin "1") (pinfunction "A_1") (pintype "passive"))
      (node (ref "L58") (pin "2") (pinfunction "K_2") (pintype "passive"))
    )
    (net (code "58") (name "Net-(L58-A)") (class "Default")
      (node (ref "L58") (pin "1") (pinfunction "A_1") (pintype "passive"))
      (node (ref "L59") (pin "2") (pinfunction "K_2") (pintype "passive"))
    )
    (net (code "59") (name "Net-(L59-A)") (class "Default")
      (node (ref "L59") (pin "1") (pinfunction "A_1") (pintype "passive"))
      (node (ref "L60") (pin "2") (pinfunction "K_2") (pintype "passive"))
    )
    (net (code "60") (name "Net-(L61-A)") (class "Default")
      (node (ref "L61") (pin "1") (pinfunction "A_1") (pintype "passive"))
      (node (ref "L62") (pin "2") (pinfunction "K_2") (pintype "passive"))
    )
    (net (code "61") (name "Net-(L62-A)") (class "Default")
      (node (ref "L62") (pin "1") (pinfunction "A_1") (pintype "passive"))
      (node (ref "L63") (pin "2") (pinfunction "K_2") (pintype "passive"))
    )
    (net (code "62") (name "Net-(L63-A)") (class "Default")
      (node (ref "L63") (pin "1") (pinfunction "A_1") (pintype "passive"))
      (node (ref "L64") (pin "2") (pinfunction "K_2") (pintype "passive"))
    )
    (net (code "63") (name "Net-(L65-A)") (class "Default")
      (node (ref "L65") (pin "1") (pinfunction "A_1") (pintype "passive"))
      (node (ref "L66") (pin "2") (pinfunction "K_2") (pintype "passive"))
    )
    (net (code "64") (name "Net-(L66-A)") (class "Default")
      (node (ref "L66") (pin "1") (pinfunction "A_1") (pintype "passive"))
      (node (ref "L67") (pin "2") (pinfunction "K_2") (pintype "passive"))
    )
    (net (code "65") (name "Net-(L67-A)") (class "Default")
      (node (ref "L67") (pin "1") (pinfunction "A_1") (pintype "passive"))
      (node (ref "L68") (pin "2") (pinfunction "K_2") (pintype "passive"))
    )
    (net (code "66") (name "Net-(L69-A)") (class "Default")
      (node (ref "L69") (pin "1") (pinfunction "A_1") (pintype "passive"))
      (node (ref "L70") (pin "2") (pinfunction "K_2") (pintype "passive"))
    )
    (net (code "67") (name "Net-(L70-A)") (class "Default")
      (node (ref "L70") (pin "1") (pinfunction "A_1") (pintype "passive"))
      (node (ref "L71") (pin "2") (pinfunction "K_2") (pintype "passive"))
    )
    (net (code "68") (name "Net-(L71-A)") (class "Default")
      (node (ref "L71") (pin "1") (pinfunction "A_1") (pintype "passive"))
      (node (ref "L72") (pin "2") (pinfunction "K_2") (pintype "passive"))
    )
    (net (code "69") (name "Net-(L73-A)") (class "Default")
      (node (ref "L73") (pin "1") (pinfunction "A_1") (pintype "passive"))
      (node (ref "L74") (pin "2") (pinfunction "K_2") (pintype "passive"))
    )
    (net (code "70") (name "Net-(L74-A)") (class "Default")
      (node (ref "L74") (pin "1") (pinfunction "A_1") (pintype "passive"))
      (node (ref "L75") (pin "2") (pinfunction "K_2") (pintype "passive"))
    )
    (net (code "71") (name "Net-(L75-A)") (class "Default")
      (node (ref "L75") (pin "1") (pinfunction "A_1") (pintype "passive"))
      (node (ref "L76") (pin "2") (pinfunction "K_2") (pintype "passive"))
    )
    (net (code "72") (name "Net-(L77-A)") (class "Default")
      (node (ref "L77") (pin "1") (pinfunction "A_1") (pintype "passive"))
      (node (ref "L78") (pin "2") (pinfunction "K_2") (pintype "passive"))
    )
    (net (code "73") (name "Net-(L78-A)") (class "Default")
      (node (ref "L78") (pin "1") (pinfunction "A_1") (pintype "passive"))
      (node (ref "L79") (pin "2") (pinfunction "K_2") (pintype "passive"))
    )
    (net (code "74") (name "Net-(L79-A)") (class "Default")
      (node (ref "L79") (pin "1") (pinfunction "A_1") (pintype "passive"))
      (node (ref "L80") (pin "2") (pinfunction "K_2") (pintype "passive"))
    )
    (net (code "75") (name "Net-(L81-A)") (class "Default")
      (node (ref "L81") (pin "1") (pinfunction "A_1") (pintype "passive"))
      (node (ref "L82") (pin "2") (pinfunction "K_2") (pintype "passive"))
    )
    (net (code "76") (name "Net-(L82-A)") (class "Default")
      (node (ref "L82") (pin "1") (pinfunction "A_1") (pintype "passive"))
      (node (ref "L83") (pin "2") (pinfunction "K_2") (pintype "passive"))
    )
    (net (code "77") (name "Net-(L83-A)") (class "Default")
      (node (ref "L83") (pin "1") (pinfunction "A_1") (pintype "passive"))
      (node (ref "L84") (pin "2") (pinfunction "K_2") (pintype "passive"))
    )
    (net (code "78") (name "Net-(L85-A)") (class "Default")
      (node (ref "L85") (pin "1") (pinfunction "A_1") (pintype "passive"))
      (node (ref "L86") (pin "2") (pinfunction "K_2") (pintype "passive"))
    )
    (net (code "79") (name "Net-(L86-A)") (class "Default")
      (node (ref "L86") (pin "1") (pinfunction "A_1") (pintype "passive"))
      (node (ref "L87") (pin "2") (pinfunction "K_2") (pintype "passive"))
    )
    (net (code "80") (name "Net-(L87-A)") (class "Default")
      (node (ref "L87") (pin "1") (pinfunction "A_1") (pintype "passive"))
      (node (ref "L88") (pin "2") (pinfunction "K_2") (pintype "passive"))
    )
    (net (code "81") (name "Net-(L89-A)") (class "Default")
      (node (ref "L89") (pin "1") (pinfunction "A_1") (pintype "passive"))
      (node (ref "L90") (pin "2") (pinfunction "K_2") (pintype "passive"))
    )
    (net (code "82") (name "Net-(L90-A)") (class "Default")
      (node (ref "L90") (pin "1") (pinfunction "A_1") (pintype "passive"))
      (node (ref "L91") (pin "2") (pinfunction "K_2") (pintype "passive"))
    )
    (net (code "83") (name "Net-(L91-A)") (class "Default")
      (node (ref "L91") (pin "1") (pinfunction "A_1") (pintype "passive"))
      (node (ref "L92") (pin "2") (pinfunction "K_2") (pintype "passive"))
    )
    (net (code "84") (name "Net-(L93-A)") (class "Default")
      (node (ref "L93") (pin "1") (pinfunction "A_1") (pintype "passive"))
      (node (ref "L94") (pin "2") (pinfunction "K_2") (pintype "passive"))
    )
    (net (code "85") (name "Net-(L94-A)") (class "Default")
      (node (ref "L94") (pin "1") (pinfunction "A_1") (pintype "passive"))
      (node (ref "L95") (pin "2") (pinfunction "K_2") (pintype "passive"))
    )
    (net (code "86") (name "Net-(L95-A)") (class "Default")
      (node (ref "L95") (pin "1") (pinfunction "A_1") (pintype "passive"))
      (node (ref "L96") (pin "2") (pinfunction "K_2") (pintype "passive"))
    )
    (net (code "87") (name "Net-(L97-A)") (class "Default")
      (node (ref "L97") (pin "1") (pinfunction "A_1") (pintype "passive"))
      (node (ref "L98") (pin "2") (pinfunction "K_2") (pintype "passive"))
    )
    (net (code "88") (name "Net-(L98-A)") (class "Default")
      (node (ref "L98") (pin "1") (pinfunction "A_1") (pintype "passive"))
      (node (ref "L99") (pin "2") (pinfunction "K_2") (pintype "passive"))
    )
    (net (code "89") (name "Net-(L100-K)") (class "Default")
      (node (ref "L100") (pin "2") (pinfunction "K_2") (pintype "passive"))
      (node (ref "L99") (pin "1") (pinfunction "A_1") (pintype "passive"))
    )
    (net (code "90") (name "Net-(U1-IN)") (class "Default")
      (node (ref "R1") (pin "2") (pinfunction "2_2") (pintype "passive"))
      (node (ref "U1") (pin "3") (pinfunction "IN_3") (pintype "passive"))
    )
    (net (code "91") (name "Net-(U2-QA)") (class "Default")
      (node (ref "U2") (pin "15") (pinfunction "QA_15") (pintype "tri_state"))
      (node (ref "U3") (pin "8") (pinfunction "I8_8") (pintype "input"))
    )
    (net (code "92") (name "Net-(U2-QB)") (class "Default")
      (node (ref "U2") (pin "1") (pinfunction "QB_1") (pintype "tri_state"))
      (node (ref "U3") (pin "7") (pinfunction "I7_7") (pintype "input"))
    )
    (net (code "93") (name "Net-(U2-QC)") (class "Default")
      (node (ref "U2") (pin "2") (pinfunction "QC_2") (pintype "tri_state"))
      (node (ref "U3") (pin "6") (pinfunction "I6_6") (pintype "input"))
    )
    (net (code "94") (name "Net-(U2-QD)") (class "Default")
      (node (ref "U2") (pin "3") (pinfunction "QD_3") (pintype "tri_state"))
      (node (ref "U3") (pin "5") (pinfunction "I5_5") (pintype "input"))
    )
    (net (code "95") (name "Net-(U2-QE)") (class "Default")
      (node (ref "U2") (pin "4") (pinfunction "QE_4") (pintype "tri_state"))
      (node (ref "U3") (pin "4") (pinfunction "I4_4") (pintype "input"))
    )
    (net (code "96") (name "Net-(U2-QF)") (class "Default")
      (node (ref "U2") (pin "5") (pinfunction "QF_5") (pintype "tri_state"))
      (node (ref "U3") (pin "3") (pinfunction "I3_3") (pintype "input"))
    )
    (net (code "97") (name "Net-(U2-QG)") (class "Default")
      (node (ref "U2") (pin "6") (pinfunction "QG_6") (pintype "tri_state"))
      (node (ref "U3") (pin "2") (pinfunction "I2_2") (pintype "input"))
    )
    (net (code "98") (name "Net-(U3-O2)") (class "Default")
      (node (ref "R8") (pin "1") (pinfunction "1_1") (pintype "passive"))
      (node (ref "U3") (pin "17") (pinfunction "O2_17") (pintype "open_collector"))
    )
    (net (code "99") (name "Net-(U3-O3)") (class "Default")
      (node (ref "R7") (pin "1") (pinfunction "1_1") (pintype "passive"))
      (node (ref "U3") (pin "16") (pinfunction "O3_16") (pintype "open_collector"))
    )
    (net (code "100") (name "Net-(U3-O4)") (class "Default")
      (node (ref "R6") (pin "1") (pinfunction "1_1") (pintype "passive"))
      (node (ref "U3") (pin "15") (pinfunction "O4_15") (pintype "open_collector"))
    )
    (net (code "101") (name "Net-(U3-O5)") (class "Default")
      (node (ref "R5") (pin "1") (pinfunction "1_1") (pintype "passive"))
      (node (ref "U3") (pin "14") (pinfunction "O5_14") (pintype "open_collector"))
    )
    (net (code "102") (name "Net-(U3-O6)") (class "Default")
      (node (ref "R4") (pin "1") (pinfunction "1_1") (pintype "passive"))
      (node (ref "U3") (pin "13") (pinfunction "O6_13") (pintype "open_collector"))
    )
    (net (code "103") (name "Net-(U3-O7)") (class "Default")
      (node (ref "R3") (pin "1") (pinfunction "1_1") (pintype "passive"))
      (node (ref "U3") (pin "12") (pinfunction "O7_12") (pintype "open_collector"))
    )
    (net (code "104") (name "Net-(U3-O8)") (class "Default")
      (node (ref "R2") (pin "1") (pinfunction "1_1") (pintype "passive"))
      (node (ref "U3") (pin "11") (pinfunction "O8_11") (pintype "open_collector"))
    )
    (net (code "105") (name "unconnected-(U2-QH-Pad7)") (class "Default")
      (node (ref "U2") (pin "7") (pinfunction "QH_7") (pintype "tri_state+no_connect"))
    )
    (net (code "106") (name "unconnected-(U3-COM-Pad10)") (class "Default")
      (node (ref "U3") (pin "10") (pinfunction "COM_10") (pintype "passive+no_connect"))
    )
    (net (code "107") (name "unconnected-(U3-I1-Pad1)") (class "Default")
      (node (ref "U3") (pin "1") (pinfunction "I1_1") (pintype "input+no_connect"))
    )
    (net (code "108") (name "unconnected-(U3-O1-Pad18)") (class "Default")
      (node (ref "U3") (pin "18") (pinfunction "O1_18") (pintype "open_collector+no_connect"))
    )
  )
)
